# SDRAM.net
KiCad netlist of a schematic drawn in Altium Designer
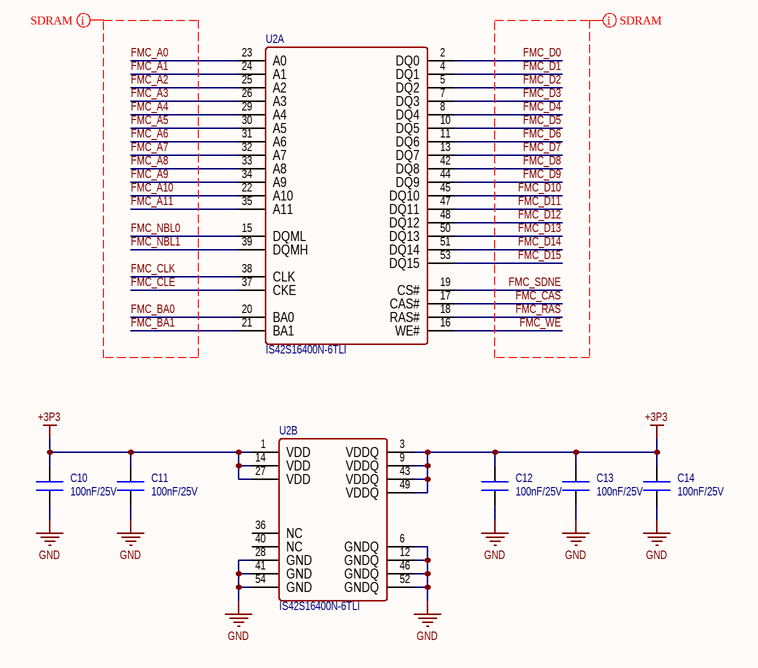
[diagram p0: SDRAM.SchDoc]

(export (version "E")
  (design (tool "Eeschema 10.0.6"))
  (components
    (comp (ref "C10")
      (value "100nF/25V")
      (footprint "CN-SMD-0603")
      (description "CAP CER 0.1UF 25V X7R 0603")
      (libsource (lib "Library") (part "CN"))
    )
    (comp (ref "C11")
      (value "100nF/25V")
      (footprint "CN-SMD-0603")
      (description "CAP CER 0.1UF 25V X7R 0603")
      (libsource (lib "Library") (part "CN"))
    )
    (comp (ref "C12")
      (value "100nF/25V")
      (footprint "CN-SMD-0603")
      (description "CAP CER 0.1UF 25V X7R 0603")
      (libsource (lib "Library") (part "CN"))
    )
    (comp (ref "C13")
      (value "100nF/25V")
      (footprint "CN-SMD-0603")
      (description "CAP CER 0.1UF 25V X7R 0603")
      (libsource (lib "Library") (part "CN"))
    )
    (comp (ref "C14")
      (value "100nF/25V")
      (footprint "CN-SMD-0603")
      (description "CAP CER 0.1UF 25V X7R 0603")
      (libsource (lib "Library") (part "CN"))
    )
    (comp (ref "U2")
      (value "IS42S16400N-6TLI")
      (footprint "TSOP80P1180X100-54N")
      (description "1 Meg Bits x 16 Bits x 4 Banks (64-MBIT) SYNCHRONOUS DYNAMIC RAM")
      (libsource (lib "Library") (part "IS42S16400N-6TLI"))
    )
  )
  (nets
    (net (code "1") (name "+3P3") (class "Default")
      (node (ref "C10") (pin "2") (pinfunction "2_2") (pintype "passive"))
      (node (ref "C11") (pin "2") (pinfunction "2_2") (pintype "passive"))
      (node (ref "C12") (pin "2") (pinfunction "2_2") (pintype "passive"))
      (node (ref "C13") (pin "2") (pinfunction "2_2") (pintype "passive"))
      (node (ref "C14") (pin "2") (pinfunction "2_2") (pintype "passive"))
      (node (ref "U2") (pin "1") (pinfunction "VDD_1") (pintype "passive"))
      (node (ref "U2") (pin "14") (pinfunction "VDD_14") (pintype "passive"))
      (node (ref "U2") (pin "27") (pinfunction "VDD_27") (pintype "passive"))
      (node (ref "U2") (pin "3") (pinfunction "VDDQ_3") (pintype "passive"))
      (node (ref "U2") (pin "43") (pinfunction "VDDQ_43") (pintype "passive"))
      (node (ref "U2") (pin "49") (pinfunction "VDDQ_49") (pintype "passive"))
      (node (ref "U2") (pin "9") (pinfunction "VDDQ_9") (pintype "passive"))
    )
    (net (code "2") (name "/FMC_A0") (class "Default")
      (node (ref "U2") (pin "23") (pinfunction "A0_23") (pintype "passive"))
    )
    (net (code "3") (name "/FMC_A1") (class "Default")
      (node (ref "U2") (pin "24") (pinfunction "A1_24") (pintype "passive"))
    )
    (net (code "4") (name "/FMC_A2") (class "Default")
      (node (ref "U2") (pin "25") (pinfunction "A2_25") (pintype "passive"))
    )
    (net (code "5") (name "/FMC_A3") (class "Default")
      (node (ref "U2") (pin "26") (pinfunction "A3_26") (pintype "passive"))
    )
    (net (code "6") (name "/FMC_A4") (class "Default")
      (node (ref "U2") (pin "29") (pinfunction "A4_29") (pintype "passive"))
    )
    (net (code "7") (name "/FMC_A5") (class "Default")
      (node (ref "U2") (pin "30") (pinfunction "A5_30") (pintype "passive"))
    )
    (net (code "8") (name "/FMC_A6") (class "Default")
      (node (ref "U2") (pin "31") (pinfunction "A6_31") (pintype "passive"))
    )
    (net (code "9") (name "/FMC_A7") (class "Default")
      (node (ref "U2") (pin "32") (pinfunction "A7_32") (pintype "passive"))
    )
    (net (code "10") (name "/FMC_A8") (class "Default")
      (node (ref "U2") (pin "33") (pinfunction "A8_33") (pintype "passive"))
    )
    (net (code "11") (name "/FMC_A9") (class "Default")
      (node (ref "U2") (pin "34") (pinfunction "A9_34") (pintype "passive"))
    )
    (net (code "12") (name "/FMC_A10") (class "Default")
      (node (ref "U2") (pin "22") (pinfunction "A10_22") (pintype "passive"))
    )
    (net (code "13") (name "/FMC_A11") (class "Default")
      (node (ref "U2") (pin "35") (pinfunction "A11_35") (pintype "passive"))
    )
    (net (code "14") (name "/FMC_BA0") (class "Default")
      (node (ref "U2") (pin "20") (pinfunction "BA0_20") (pintype "passive"))
    )
    (net (code "15") (name "/FMC_BA1") (class "Default")
      (node (ref "U2") (pin "21") (pinfunction "BA1_21") (pintype "passive"))
    )
    (net (code "16") (name "/FMC_CAS") (class "Default")
      (node (ref "U2") (pin "17") (pinfunction "CAS#_17") (pintype "passive"))
    )
    (net (code "17") (name "/FMC_CLE") (class "Default")
      (node (ref "U2") (pin "37") (pinfunction "CKE_37") (pintype "passive"))
    )
    (net (code "18") (name "/FMC_CLK") (class "Default")
      (node (ref "U2") (pin "38") (pinfunction "CLK_38") (pintype "passive"))
    )
    (net (code "19") (name "/FMC_D0") (class "Default")
      (node (ref "U2") (pin "2") (pinfunction "DQ0_2") (pintype "passive"))
    )
    (net (code "20") (name "/FMC_D1") (class "Default")
      (node (ref "U2") (pin "4") (pinfunction "DQ1_4") (pintype "passive"))
    )
    (net (code "21") (name "/FMC_D2") (class "Default")
      (node (ref "U2") (pin "5") (pinfunction "DQ2_5") (pintype "passive"))
    )
    (net (code "22") (name "/FMC_D3") (class "Default")
      (node (ref "U2") (pin "7") (pinfunction "DQ3_7") (pintype "passive"))
    )
    (net (code "23") (name "/FMC_D4") (class "Default")
      (node (ref "U2") (pin "8") (pinfunction "DQ4_8") (pintype "passive"))
    )
    (net (code "24") (name "/FMC_D5") (class "Default")
      (node (ref "U2") (pin "10") (pinfunction "DQ5_10") (pintype "passive"))
    )
    (net (code "25") (name "/FMC_D6") (class "Default")
      (node (ref "U2") (pin "11") (pinfunction "DQ6_11") (pintype "passive"))
    )
    (net (code "26") (name "/FMC_D7") (class "Default")
      (node (ref "U2") (pin "13") (pinfunction "DQ7_13") (pintype "passive"))
    )
    (net (code "27") (name "/FMC_D8") (class "Default")
      (node (ref "U2") (pin "42") (pinfunction "DQ8_42") (pintype "passive"))
    )
    (net (code "28") (name "/FMC_D9") (class "Default")
      (node (ref "U2") (pin "44") (pinfunction "DQ9_44") (pintype "passive"))
    )
    (net (code "29") (name "/FMC_D10") (class "Default")
      (node (ref "U2") (pin "45") (pinfunction "DQ10_45") (pintype "passive"))
    )
    (net (code "30") (name "/FMC_D11") (class "Default")
      (node (ref "U2") (pin "47") (pinfunction "DQ11_47") (pintype "passive"))
    )
    (net (code "31") (name "/FMC_D12") (class "Default")
      (node (ref "U2") (pin "48") (pinfunction "DQ12_48") (pintype "passive"))
    )
    (net (code "32") (name "/FMC_D13") (class "Default")
      (node (ref "U2") (pin "50") (pinfunction "DQ13_50") (pintype "passive"))
    )
    (net (code "33") (name "/FMC_D14") (class "Default")
      (node (ref "U2") (pin "51") (pinfunction "DQ14_51") (pintype "passive"))
    )
    (net (code "34") (name "/FMC_D15") (class "Default")
      (node (ref "U2") (pin "53") (pinfunction "DQ15_53") (pintype "passive"))
    )
    (net (code "35") (name "/FMC_NBL0") (class "Default")
      (node (ref "U2") (pin "15") (pinfunction "DQML_15") (pintype "passive"))
    )
    (net (code "36") (name "/FMC_NBL1") (class "Default")
      (node (ref "U2") (pin "39") (pinfunction "DQMH_39") (pintype "passive"))
    )
    (net (code "37") (name "/FMC_RAS") (class "Default")
      (node (ref "U2") (pin "18") (pinfunction "RAS#_18") (pintype "passive"))
    )
    (net (code "38") (name "/FMC_SDNE") (class "Default")
      (node (ref "U2") (pin "19") (pinfunction "CS#_19") (pintype "passive"))
    )
    (net (code "39") (name "/FMC_WE") (class "Default")
      (node (ref "U2") (pin "16") (pinfunction "WE#_16") (pintype "passive"))
    )
    (net (code "40") (name "GND") (class "Default")
      (node (ref "C10") (pin "1") (pinfunction "1_1") (pintype "passive"))
      (node (ref "C11") (pin "1") (pinfunction "1_1") (pintype "passive"))
      (node (ref "C12") (pin "1") (pinfunction "1_1") (pintype "passive"))
      (node (ref "C13") (pin "1") (pinfunction "1_1") (pintype "passive"))
      (node (ref "C14") (pin "1") (pinfunction "1_1") (pintype "passive"))
      (node (ref "U2") (pin "12") (pinfunction "GNDQ_12") (pintype "passive"))
      (node (ref "U2") (pin "28") (pinfunction "GND_28") (pintype "passive"))
      (node (ref "U2") (pin "41") (pinfunction "GND_41") (pintype "passive"))
      (node (ref "U2") (pin "46") (pinfunction "GNDQ_46") (pintype "passive"))
      (node (ref "U2") (pin "52") (pinfunction "GNDQ_52") (pintype "passive"))
      (node (ref "U2") (pin "54") (pinfunction "GND_54") (pintype "passive"))
      (node (ref "U2") (pin "6") (pinfunction "GNDQ_6") (pintype "passive"))
    )
    (net (code "41") (name "unconnected-(U2B-NC-Pad36)") (class "Default")
      (node (ref "U2") (pin "36") (pinfunction "NC_36") (pintype "passive"))
    )
    (net (code "42") (name "unconnected-(U2B-NC-Pad40)") (class "Default")
      (node (ref "U2") (pin "40") (pinfunction "NC_40") (pintype "passive"))
    )
  )
)
